# ecocar_CVM_R1.net
KiCad netlist of a schematic drawn in EAGLE
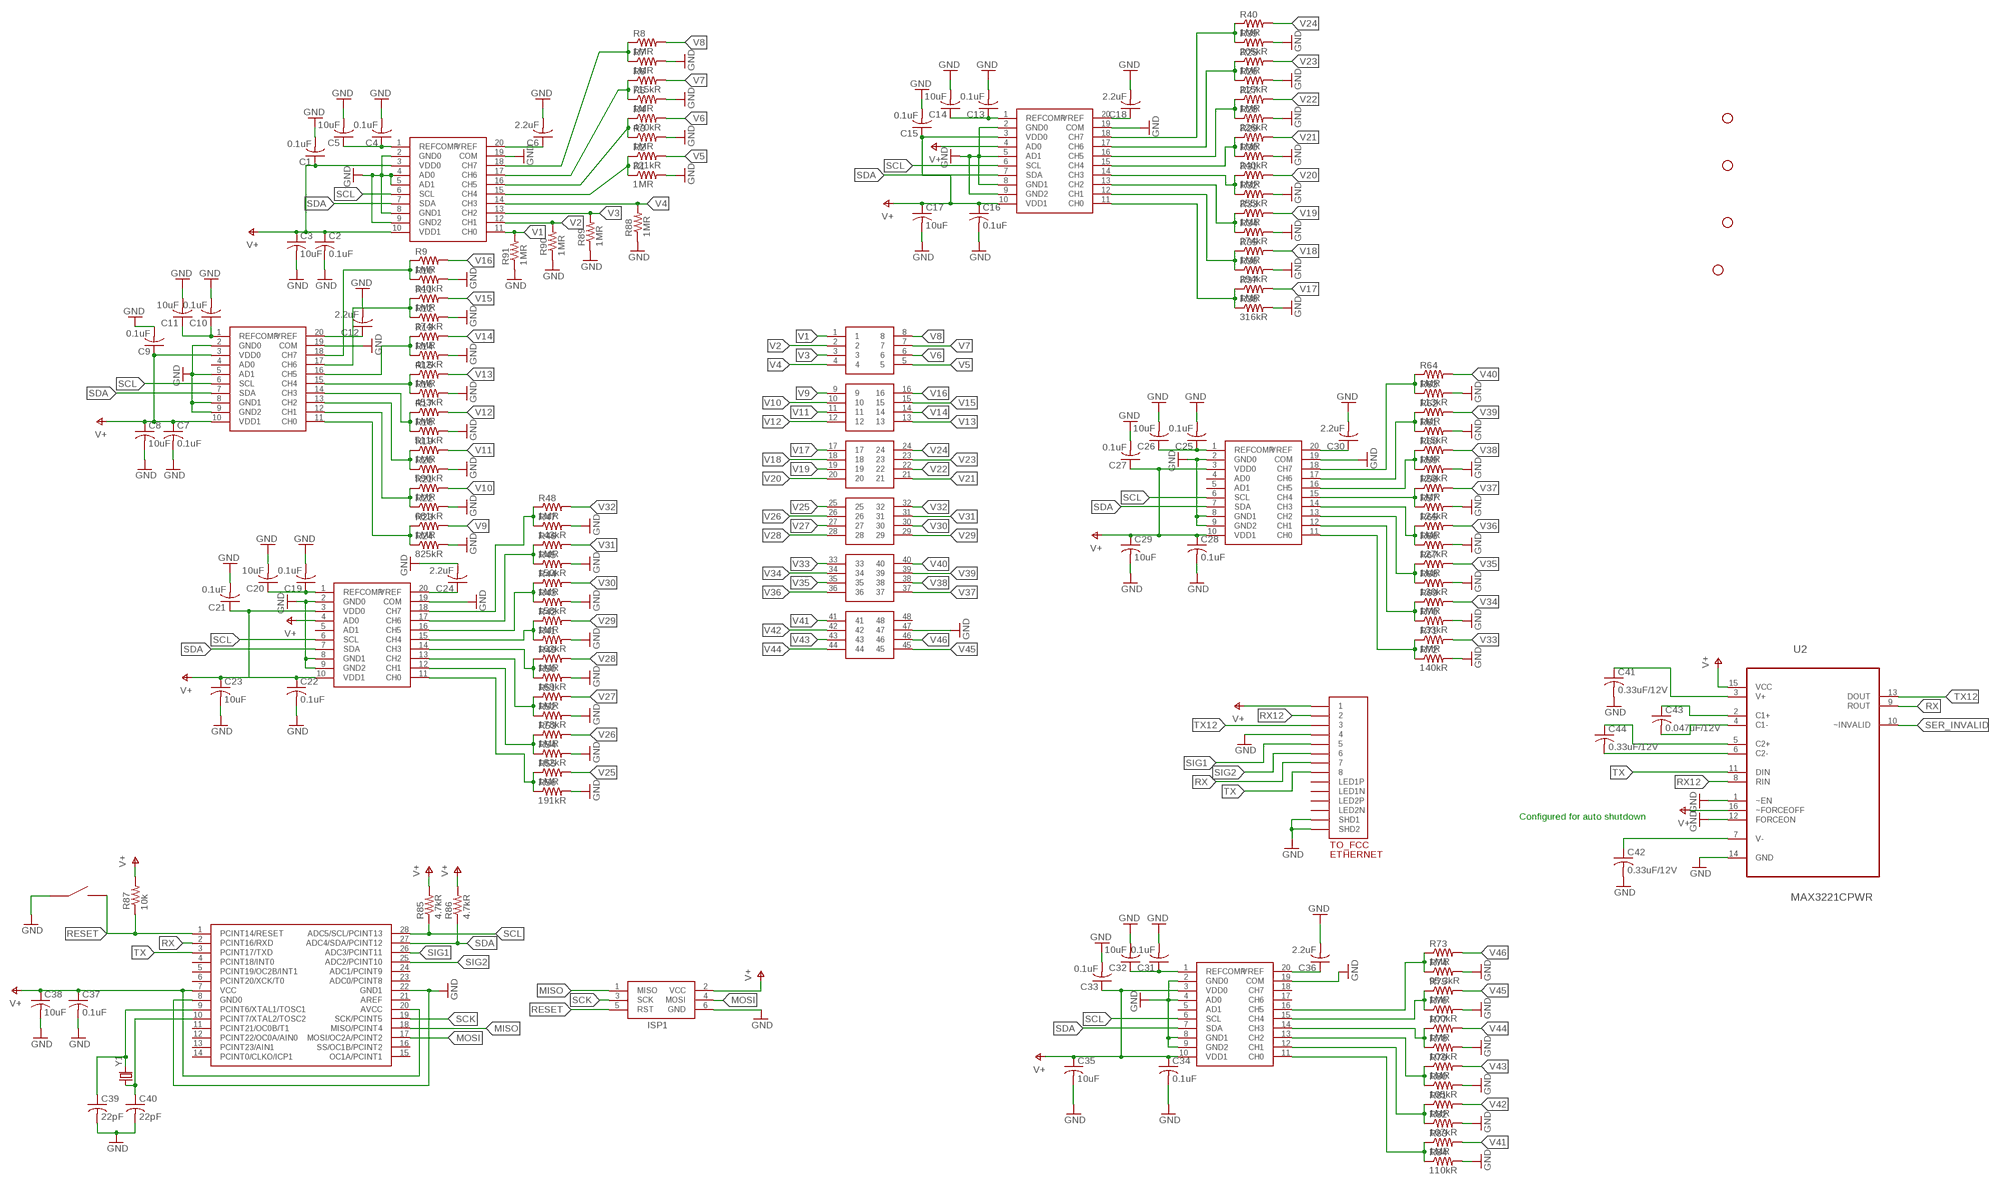
[diagram p0: schematic, sheet 1]

(export (version "E")
  (design (tool "Eeschema 10.0.6"))
  (components
    (comp (ref "0001000")
      (value "LTC2309")
      (footprint "eagle-import:TSSOP20")
      (libsource (lib "eagle-import") (part "LTC2309HF#PBF"))
    )
    (comp (ref "0001001")
      (value "LTC2309")
      (footprint "eagle-import:TSSOP20")
      (libsource (lib "eagle-import") (part "LTC2309HF#PBF"))
    )
    (comp (ref "0001010")
      (value "LTC2309")
      (footprint "eagle-import:TSSOP20")
      (libsource (lib "eagle-import") (part "LTC2309HF#PBF"))
    )
    (comp (ref "0001011")
      (value "LTC2309")
      (footprint "eagle-import:TSSOP20")
      (libsource (lib "eagle-import") (part "LTC2309HF#PBF"))
    )
    (comp (ref "0011000")
      (value "LTC2309")
      (footprint "eagle-import:TSSOP20")
      (libsource (lib "eagle-import") (part "LTC2309HF#PBF"))
    )
    (comp (ref "0011001")
      (value "LTC2309")
      (footprint "eagle-import:TSSOP20")
      (libsource (lib "eagle-import") (part "LTC2309HF#PBF"))
    )
    (comp (ref "C1")
      (value "0.1uF")
      (footprint "eagle-import:C0805")
      (libsource (lib "eagle-import") (part "rcl_C-USC0805"))
    )
    (comp (ref "C2")
      (value "0.1uF")
      (footprint "eagle-import:C0805")
      (libsource (lib "eagle-import") (part "rcl_C-USC0805"))
    )
    (comp (ref "C3")
      (value "10uF")
      (footprint "eagle-import:C0805")
      (libsource (lib "eagle-import") (part "rcl_C-USC0805"))
    )
    (comp (ref "C4")
      (value "0.1uF")
      (footprint "eagle-import:C0805")
      (libsource (lib "eagle-import") (part "rcl_C-USC0805"))
    )
    (comp (ref "C5")
      (value "10uF")
      (footprint "eagle-import:C0805")
      (libsource (lib "eagle-import") (part "rcl_C-USC0805"))
    )
    (comp (ref "C6")
      (value "2.2uF")
      (footprint "eagle-import:C0805")
      (libsource (lib "eagle-import") (part "rcl_C-USC0805"))
    )
    (comp (ref "C7")
      (value "0.1uF")
      (footprint "eagle-import:C0805")
      (libsource (lib "eagle-import") (part "rcl_C-USC0805"))
    )
    (comp (ref "C8")
      (value "10uF")
      (footprint "eagle-import:C0805")
      (libsource (lib "eagle-import") (part "rcl_C-USC0805"))
    )
    (comp (ref "C9")
      (value "0.1uF")
      (footprint "eagle-import:C0805")
      (libsource (lib "eagle-import") (part "rcl_C-USC0805"))
    )
    (comp (ref "C10")
      (value "0.1uF")
      (footprint "eagle-import:C0805")
      (libsource (lib "eagle-import") (part "rcl_C-USC0805"))
    )
    (comp (ref "C11")
      (value "10uF")
      (footprint "eagle-import:C0805")
      (libsource (lib "eagle-import") (part "rcl_C-USC0805"))
    )
    (comp (ref "C12")
      (value "2.2uF")
      (footprint "eagle-import:C0805")
      (libsource (lib "eagle-import") (part "rcl_C-USC0805"))
    )
    (comp (ref "C13")
      (value "0.1uF")
      (footprint "eagle-import:C0805")
      (libsource (lib "eagle-import") (part "rcl_C-USC0805"))
    )
    (comp (ref "C14")
      (value "10uF")
      (footprint "eagle-import:C0805")
      (libsource (lib "eagle-import") (part "rcl_C-USC0805"))
    )
    (comp (ref "C15")
      (value "0.1uF")
      (footprint "eagle-import:C0805")
      (libsource (lib "eagle-import") (part "rcl_C-USC0805"))
    )
    (comp (ref "C16")
      (value "0.1uF")
      (footprint "eagle-import:C0805")
      (libsource (lib "eagle-import") (part "rcl_C-USC0805"))
    )
    (comp (ref "C17")
      (value "10uF")
      (footprint "eagle-import:C0805")
      (libsource (lib "eagle-import") (part "rcl_C-USC0805"))
    )
    (comp (ref "C18")
      (value "2.2uF")
      (footprint "eagle-import:C0805")
      (libsource (lib "eagle-import") (part "rcl_C-USC0805"))
    )
    (comp (ref "C19")
      (value "0.1uF")
      (footprint "eagle-import:C0805")
      (libsource (lib "eagle-import") (part "rcl_C-USC0805"))
    )
    (comp (ref "C20")
      (value "10uF")
      (footprint "eagle-import:C0805")
      (libsource (lib "eagle-import") (part "rcl_C-USC0805"))
    )
    (comp (ref "C21")
      (value "0.1uF")
      (footprint "eagle-import:C0805")
      (libsource (lib "eagle-import") (part "rcl_C-USC0805"))
    )
    (comp (ref "C22")
      (value "0.1uF")
      (footprint "eagle-import:C0805")
      (libsource (lib "eagle-import") (part "rcl_C-USC0805"))
    )
    (comp (ref "C23")
      (value "10uF")
      (footprint "eagle-import:C0805")
      (libsource (lib "eagle-import") (part "rcl_C-USC0805"))
    )
    (comp (ref "C24")
      (value "2.2uF")
      (footprint "eagle-import:C0805")
      (libsource (lib "eagle-import") (part "rcl_C-USC0805"))
    )
    (comp (ref "C25")
      (value "0.1uF")
      (footprint "eagle-import:C0805")
      (libsource (lib "eagle-import") (part "rcl_C-USC0805"))
    )
    (comp (ref "C26")
      (value "10uF")
      (footprint "eagle-import:C0805")
      (libsource (lib "eagle-import") (part "rcl_C-USC0805"))
    )
    (comp (ref "C27")
      (value "0.1uF")
      (footprint "eagle-import:C0805")
      (libsource (lib "eagle-import") (part "rcl_C-USC0805"))
    )
    (comp (ref "C28")
      (value "0.1uF")
      (footprint "eagle-import:C0805")
      (libsource (lib "eagle-import") (part "rcl_C-USC0805"))
    )
    (comp (ref "C29")
      (value "10uF")
      (footprint "eagle-import:C0805")
      (libsource (lib "eagle-import") (part "rcl_C-USC0805"))
    )
    (comp (ref "C30")
      (value "2.2uF")
      (footprint "eagle-import:C0805")
      (libsource (lib "eagle-import") (part "rcl_C-USC0805"))
    )
    (comp (ref "C31")
      (value "0.1uF")
      (footprint "eagle-import:C0805")
      (libsource (lib "eagle-import") (part "rcl_C-USC0805"))
    )
    (comp (ref "C32")
      (value "10uF")
      (footprint "eagle-import:C0805")
      (libsource (lib "eagle-import") (part "rcl_C-USC0805"))
    )
    (comp (ref "C33")
      (value "0.1uF")
      (footprint "eagle-import:C0805")
      (libsource (lib "eagle-import") (part "rcl_C-USC0805"))
    )
    (comp (ref "C34")
      (value "0.1uF")
      (footprint "eagle-import:C0805")
      (libsource (lib "eagle-import") (part "rcl_C-USC0805"))
    )
    (comp (ref "C35")
      (value "10uF")
      (footprint "eagle-import:C0805")
      (libsource (lib "eagle-import") (part "rcl_C-USC0805"))
    )
    (comp (ref "C36")
      (value "2.2uF")
      (footprint "eagle-import:C0805")
      (libsource (lib "eagle-import") (part "rcl_C-USC0805"))
    )
    (comp (ref "C37")
      (value "0.1uF")
      (footprint "eagle-import:C0805")
      (libsource (lib "eagle-import") (part "rcl_C-USC0805"))
    )
    (comp (ref "C38")
      (value "10uF")
      (footprint "eagle-import:C0805")
      (libsource (lib "eagle-import") (part "rcl_C-USC0805"))
    )
    (comp (ref "C39")
      (value "22pF")
      (footprint "eagle-import:C0805")
      (libsource (lib "eagle-import") (part "rcl_C-USC0805"))
    )
    (comp (ref "C40")
      (value "22pF")
      (footprint "eagle-import:C0805")
      (libsource (lib "eagle-import") (part "rcl_C-USC0805"))
    )
    (comp (ref "C41")
      (value "0.33uF/12V")
      (footprint "eagle-import:C0805")
      (libsource (lib "eagle-import") (part "C-USC0805"))
    )
    (comp (ref "C42")
      (value "0.33uF/12V")
      (footprint "eagle-import:C0805")
      (libsource (lib "eagle-import") (part "C-USC0805"))
    )
    (comp (ref "C43")
      (value "0.047uF/12V")
      (footprint "eagle-import:C0805")
      (libsource (lib "eagle-import") (part "C-USC0805"))
    )
    (comp (ref "C44")
      (value "0.33uF/12V")
      (footprint "eagle-import:C0805")
      (libsource (lib "eagle-import") (part "C-USC0805"))
    )
    (comp (ref "ISP1")
      (value "AVRISP-BOX")
      (footprint "eagle-import:AVRISP-BOX")
      (libsource (lib "eagle-import") (part "AVRISP-BOX"))
    )
    (comp (ref "R1")
      (value "1MR")
      (footprint "eagle-import:R0805")
      (libsource (lib "eagle-import") (part "R-US_R0805"))
    )
    (comp (ref "R2")
      (value "221kR")
      (footprint "eagle-import:R0805")
      (libsource (lib "eagle-import") (part "R-US_R0805"))
    )
    (comp (ref "R3")
      (value "1MR")
      (footprint "eagle-import:R0805")
      (libsource (lib "eagle-import") (part "R-US_R0805"))
    )
    (comp (ref "R4")
      (value "470kR")
      (footprint "eagle-import:R0805")
      (libsource (lib "eagle-import") (part "R-US_R0805"))
    )
    (comp (ref "R5")
      (value "1MR")
      (footprint "eagle-import:R0805")
      (libsource (lib "eagle-import") (part "R-US_R0805"))
    )
    (comp (ref "R6")
      (value "715kR")
      (footprint "eagle-import:R0805")
      (libsource (lib "eagle-import") (part "R-US_R0805"))
    )
    (comp (ref "R7")
      (value "1MR")
      (footprint "eagle-import:R0805")
      (libsource (lib "eagle-import") (part "R-US_R0805"))
    )
    (comp (ref "R8")
      (value "1MR")
      (footprint "eagle-import:R0805")
      (libsource (lib "eagle-import") (part "R-US_R0805"))
    )
    (comp (ref "R9")
      (value "1MR")
      (footprint "eagle-import:R0805")
      (libsource (lib "eagle-import") (part "R-US_R0805"))
    )
    (comp (ref "R10")
      (value "340kR")
      (footprint "eagle-import:R0805")
      (libsource (lib "eagle-import") (part "R-US_R0805"))
    )
    (comp (ref "R11")
      (value "1MR")
      (footprint "eagle-import:R0805")
      (libsource (lib "eagle-import") (part "R-US_R0805"))
    )
    (comp (ref "R12")
      (value "374kR")
      (footprint "eagle-import:R0805")
      (libsource (lib "eagle-import") (part "R-US_R0805"))
    )
    (comp (ref "R13")
      (value "1MR")
      (footprint "eagle-import:R0805")
      (libsource (lib "eagle-import") (part "R-US_R0805"))
    )
    (comp (ref "R14")
      (value "412kR")
      (footprint "eagle-import:R0805")
      (libsource (lib "eagle-import") (part "R-US_R0805"))
    )
    (comp (ref "R15")
      (value "1MR")
      (footprint "eagle-import:R0805")
      (libsource (lib "eagle-import") (part "R-US_R0805"))
    )
    (comp (ref "R16")
      (value "453kR")
      (footprint "eagle-import:R0805")
      (libsource (lib "eagle-import") (part "R-US_R0805"))
    )
    (comp (ref "R17")
      (value "1MR")
      (footprint "eagle-import:R0805")
      (libsource (lib "eagle-import") (part "R-US_R0805"))
    )
    (comp (ref "R18")
      (value "511kR")
      (footprint "eagle-import:R0805")
      (libsource (lib "eagle-import") (part "R-US_R0805"))
    )
    (comp (ref "R19")
      (value "1MR")
      (footprint "eagle-import:R0805")
      (libsource (lib "eagle-import") (part "R-US_R0805"))
    )
    (comp (ref "R20")
      (value "590kR")
      (footprint "eagle-import:R0805")
      (libsource (lib "eagle-import") (part "R-US_R0805"))
    )
    (comp (ref "R21")
      (value "1MR")
      (footprint "eagle-import:R0805")
      (libsource (lib "eagle-import") (part "R-US_R0805"))
    )
    (comp (ref "R22")
      (value "681kR")
      (footprint "eagle-import:R0805")
      (libsource (lib "eagle-import") (part "R-US_R0805"))
    )
    (comp (ref "R23")
      (value "1MR")
      (footprint "eagle-import:R0805")
      (libsource (lib "eagle-import") (part "R-US_R0805"))
    )
    (comp (ref "R24")
      (value "825kR")
      (footprint "eagle-import:R0805")
      (libsource (lib "eagle-import") (part "R-US_R0805"))
    )
    (comp (ref "R25")
      (value "1MR")
      (footprint "eagle-import:R0805")
      (libsource (lib "eagle-import") (part "R-US_R0805"))
    )
    (comp (ref "R26")
      (value "215kR")
      (footprint "eagle-import:R0805")
      (libsource (lib "eagle-import") (part "R-US_R0805"))
    )
    (comp (ref "R27")
      (value "1MR")
      (footprint "eagle-import:R0805")
      (libsource (lib "eagle-import") (part "R-US_R0805"))
    )
    (comp (ref "R28")
      (value "226kR")
      (footprint "eagle-import:R0805")
      (libsource (lib "eagle-import") (part "R-US_R0805"))
    )
    (comp (ref "R29")
      (value "1MR")
      (footprint "eagle-import:R0805")
      (libsource (lib "eagle-import") (part "R-US_R0805"))
    )
    (comp (ref "R30")
      (value "240kR")
      (footprint "eagle-import:R0805")
      (libsource (lib "eagle-import") (part "R-US_R0805"))
    )
    (comp (ref "R31")
      (value "1MR")
      (footprint "eagle-import:R0805")
      (libsource (lib "eagle-import") (part "R-US_R0805"))
    )
    (comp (ref "R32")
      (value "255kR")
      (footprint "eagle-import:R0805")
      (libsource (lib "eagle-import") (part "R-US_R0805"))
    )
    (comp (ref "R33")
      (value "1MR")
      (footprint "eagle-import:R0805")
      (libsource (lib "eagle-import") (part "R-US_R0805"))
    )
    (comp (ref "R34")
      (value "274kR")
      (footprint "eagle-import:R0805")
      (libsource (lib "eagle-import") (part "R-US_R0805"))
    )
    (comp (ref "R35")
      (value "1MR")
      (footprint "eagle-import:R0805")
      (libsource (lib "eagle-import") (part "R-US_R0805"))
    )
    (comp (ref "R36")
      (value "294kR")
      (footprint "eagle-import:R0805")
      (libsource (lib "eagle-import") (part "R-US_R0805"))
    )
    (comp (ref "R37")
      (value "1MR")
      (footprint "eagle-import:R0805")
      (libsource (lib "eagle-import") (part "R-US_R0805"))
    )
    (comp (ref "R38")
      (value "316kR")
      (footprint "eagle-import:R0805")
      (libsource (lib "eagle-import") (part "R-US_R0805"))
    )
    (comp (ref "R39")
      (value "205kR")
      (footprint "eagle-import:R0805")
      (libsource (lib "eagle-import") (part "R-US_R0805"))
    )
    (comp (ref "R40")
      (value "1MR")
      (footprint "eagle-import:R0805")
      (libsource (lib "eagle-import") (part "R-US_R0805"))
    )
    (comp (ref "R41")
      (value "162kR")
      (footprint "eagle-import:R0805")
      (libsource (lib "eagle-import") (part "R-US_R0805"))
    )
    (comp (ref "R42")
      (value "1MR")
      (footprint "eagle-import:R0805")
      (libsource (lib "eagle-import") (part "R-US_R0805"))
    )
    (comp (ref "R43")
      (value "158kR")
      (footprint "eagle-import:R0805")
      (libsource (lib "eagle-import") (part "R-US_R0805"))
    )
    (comp (ref "R44")
      (value "1MR")
      (footprint "eagle-import:R0805")
      (libsource (lib "eagle-import") (part "R-US_R0805"))
    )
    (comp (ref "R45")
      (value "150kR")
      (footprint "eagle-import:R0805")
      (libsource (lib "eagle-import") (part "R-US_R0805"))
    )
    (comp (ref "R46")
      (value "1MR")
      (footprint "eagle-import:R0805")
      (libsource (lib "eagle-import") (part "R-US_R0805"))
    )
    (comp (ref "R47")
      (value "143kR")
      (footprint "eagle-import:R0805")
      (libsource (lib "eagle-import") (part "R-US_R0805"))
    )
    (comp (ref "R48")
      (value "1MR")
      (footprint "eagle-import:R0805")
      (libsource (lib "eagle-import") (part "R-US_R0805"))
    )
    (comp (ref "R49")
      (value "1MR")
      (footprint "eagle-import:R0805")
      (libsource (lib "eagle-import") (part "R-US_R0805"))
    )
    (comp (ref "R50")
      (value "169kR")
      (footprint "eagle-import:R0805")
      (libsource (lib "eagle-import") (part "R-US_R0805"))
    )
    (comp (ref "R51")
      (value "1MR")
      (footprint "eagle-import:R0805")
      (libsource (lib "eagle-import") (part "R-US_R0805"))
    )
    (comp (ref "R52")
      (value "178kR")
      (footprint "eagle-import:R0805")
      (libsource (lib "eagle-import") (part "R-US_R0805"))
    )
    (comp (ref "R53")
      (value "1MR")
      (footprint "eagle-import:R0805")
      (libsource (lib "eagle-import") (part "R-US_R0805"))
    )
    (comp (ref "R54")
      (value "182kR")
      (footprint "eagle-import:R0805")
      (libsource (lib "eagle-import") (part "R-US_R0805"))
    )
    (comp (ref "R55")
      (value "1MR")
      (footprint "eagle-import:R0805")
      (libsource (lib "eagle-import") (part "R-US_R0805"))
    )
    (comp (ref "R56")
      (value "191kR")
      (footprint "eagle-import:R0805")
      (libsource (lib "eagle-import") (part "R-US_R0805"))
    )
    (comp (ref "R57")
      (value "124kR")
      (footprint "eagle-import:R0805")
      (libsource (lib "eagle-import") (part "R-US_R0805"))
    )
    (comp (ref "R58")
      (value "1MR")
      (footprint "eagle-import:R0805")
      (libsource (lib "eagle-import") (part "R-US_R0805"))
    )
    (comp (ref "R59")
      (value "120kR")
      (footprint "eagle-import:R0805")
      (libsource (lib "eagle-import") (part "R-US_R0805"))
    )
    (comp (ref "R60")
      (value "1MR")
      (footprint "eagle-import:R0805")
      (libsource (lib "eagle-import") (part "R-US_R0805"))
    )
    (comp (ref "R61")
      (value "115kR")
      (footprint "eagle-import:R0805")
      (libsource (lib "eagle-import") (part "R-US_R0805"))
    )
    (comp (ref "R62")
      (value "1MR")
      (footprint "eagle-import:R0805")
      (libsource (lib "eagle-import") (part "R-US_R0805"))
    )
    (comp (ref "R63")
      (value "113kR")
      (footprint "eagle-import:R0805")
      (libsource (lib "eagle-import") (part "R-US_R0805"))
    )
    (comp (ref "R64")
      (value "1MR")
      (footprint "eagle-import:R0805")
      (libsource (lib "eagle-import") (part "R-US_R0805"))
    )
    (comp (ref "R65")
      (value "1MR")
      (footprint "eagle-import:R0805")
      (libsource (lib "eagle-import") (part "R-US_R0805"))
    )
    (comp (ref "R66")
      (value "127kR")
      (footprint "eagle-import:R0805")
      (libsource (lib "eagle-import") (part "R-US_R0805"))
    )
    (comp (ref "R67")
      (value "1MR")
      (footprint "eagle-import:R0805")
      (libsource (lib "eagle-import") (part "R-US_R0805"))
    )
    (comp (ref "R68")
      (value "130kR")
      (footprint "eagle-import:R0805")
      (libsource (lib "eagle-import") (part "R-US_R0805"))
    )
    (comp (ref "R69")
      (value "1MR")
      (footprint "eagle-import:R0805")
      (libsource (lib "eagle-import") (part "R-US_R0805"))
    )
    (comp (ref "R70")
      (value "133kR")
      (footprint "eagle-import:R0805")
      (libsource (lib "eagle-import") (part "R-US_R0805"))
    )
    (comp (ref "R71")
      (value "1MR")
      (footprint "eagle-import:R0805")
      (libsource (lib "eagle-import") (part "R-US_R0805"))
    )
    (comp (ref "R72")
      (value "140kR")
      (footprint "eagle-import:R0805")
      (libsource (lib "eagle-import") (part "R-US_R0805"))
    )
    (comp (ref "R73")
      (value "1MR")
      (footprint "eagle-import:R0805")
      (libsource (lib "eagle-import") (part "R-US_R0805"))
    )
    (comp (ref "R74")
      (value "95.3kR")
      (footprint "eagle-import:R0805")
      (libsource (lib "eagle-import") (part "R-US_R0805"))
    )
    (comp (ref "R75")
      (value "1MR")
      (footprint "eagle-import:R0805")
      (libsource (lib "eagle-import") (part "R-US_R0805"))
    )
    (comp (ref "R76")
      (value "100kR")
      (footprint "eagle-import:R0805")
      (libsource (lib "eagle-import") (part "R-US_R0805"))
    )
    (comp (ref "R77")
      (value "1MR")
      (footprint "eagle-import:R0805")
      (libsource (lib "eagle-import") (part "R-US_R0805"))
    )
    (comp (ref "R78")
      (value "102kR")
      (footprint "eagle-import:R0805")
      (libsource (lib "eagle-import") (part "R-US_R0805"))
    )
    (comp (ref "R79")
      (value "1MR")
      (footprint "eagle-import:R0805")
      (libsource (lib "eagle-import") (part "R-US_R0805"))
    )
    (comp (ref "R80")
      (value "105kR")
      (footprint "eagle-import:R0805")
      (libsource (lib "eagle-import") (part "R-US_R0805"))
    )
    (comp (ref "R81")
      (value "1MR")
      (footprint "eagle-import:R0805")
      (libsource (lib "eagle-import") (part "R-US_R0805"))
    )
    (comp (ref "R82")
      (value "107kR")
      (footprint "eagle-import:R0805")
      (libsource (lib "eagle-import") (part "R-US_R0805"))
    )
    (comp (ref "R83")
      (value "1MR")
      (footprint "eagle-import:R0805")
      (libsource (lib "eagle-import") (part "R-US_R0805"))
    )
    (comp (ref "R84")
      (value "110kR")
      (footprint "eagle-import:R0805")
      (libsource (lib "eagle-import") (part "R-US_R0805"))
    )
    (comp (ref "R85")
      (value "4.7kR")
      (footprint "eagle-import:R0805")
      (libsource (lib "eagle-import") (part "R-US_R0805"))
    )
    (comp (ref "R86")
      (value "4.7kR")
      (footprint "eagle-import:R0805")
      (libsource (lib "eagle-import") (part "R-US_R0805"))
    )
    (comp (ref "R87")
      (value "10k")
      (footprint "eagle-import:R0805")
      (libsource (lib "eagle-import") (part "R-US_R0805"))
    )
    (comp (ref "R88")
      (value "1MR")
      (footprint "eagle-import:R0805")
      (libsource (lib "eagle-import") (part "R-US_R0805"))
    )
    (comp (ref "R89")
      (value "1MR")
      (footprint "eagle-import:R0805")
      (libsource (lib "eagle-import") (part "R-US_R0805"))
    )
    (comp (ref "R90")
      (value "1MR")
      (footprint "eagle-import:R0805")
      (libsource (lib "eagle-import") (part "R-US_R0805"))
    )
    (comp (ref "R91")
      (value "1MR")
      (footprint "eagle-import:R0805")
      (libsource (lib "eagle-import") (part "R-US_R0805"))
    )
    (comp (ref "RESET_BTN")
      (value "EG4621CT-ND")
      (footprint "eagle-import:EG4621CT-ND")
      (libsource (lib "eagle-import") (part "EG4621CT-ND"))
    )
    (comp (ref "STANDOFF1")
      (value "STAND-OFF")
      (footprint "eagle-import:STAND-OFF")
      (libsource (lib "eagle-import") (part "STAND-OFF"))
    )
    (comp (ref "STANDOFF2")
      (value "STAND-OFF")
      (footprint "eagle-import:STAND-OFF")
      (libsource (lib "eagle-import") (part "STAND-OFF"))
    )
    (comp (ref "STANDOFF3")
      (value "STAND-OFF")
      (footprint "eagle-import:STAND-OFF")
      (libsource (lib "eagle-import") (part "STAND-OFF"))
    )
    (comp (ref "STANDOFF4")
      (value "STAND-OFF")
      (footprint "eagle-import:STAND-OFF")
      (libsource (lib "eagle-import") (part "STAND-OFF"))
    )
    (comp (ref "TO_FCC")
      (value "ETHERNET")
      (footprint "eagle-import:A122645-ND")
      (libsource (lib "eagle-import") (part "ETHERNET"))
    )
    (comp (ref "U$1")
      (value "ATMEGA328P")
      (footprint "eagle-import:DIL28-3")
      (libsource (lib "eagle-import") (part "ATMEGA328P"))
    )
    (comp (ref "U$3")
      (value "6-RJ45")
      (footprint "eagle-import:48-PIN-THROUGHHOLE")
      (libsource (lib "eagle-import") (part "6-RJ45-5557572-3"))
    )
    (comp (ref "U2")
      (value "MAX3221CPWR")
      (footprint "eagle-import:SOP65P640X120-16N")
      (libsource (lib "eagle-import") (part "MAX3221CPWR"))
    )
    (comp (ref "Y1")
      (value "CRYSTALHC49US")
      (footprint "eagle-import:HC49US")
      (libsource (lib "eagle-import") (part "CRYSTALHC49US"))
    )
  )
  (nets
    (net (code "1") (name "GND") (class "Default")
      (node (ref "0001000") (pin "19") (pinfunction "COM_19") (pintype "bidirectional"))
      (node (ref "0001000") (pin "2") (pinfunction "GND0_2") (pintype "bidirectional"))
      (node (ref "0001000") (pin "4") (pinfunction "AD0_4") (pintype "bidirectional"))
      (node (ref "0001000") (pin "5") (pinfunction "AD1_5") (pintype "bidirectional"))
      (node (ref "0001000") (pin "8") (pinfunction "GND1_8") (pintype "bidirectional"))
      (node (ref "0001000") (pin "9") (pinfunction "GND2_9") (pintype "bidirectional"))
      (node (ref "0001001") (pin "19") (pinfunction "COM_19") (pintype "bidirectional"))
      (node (ref "0001001") (pin "2") (pinfunction "GND0_2") (pintype "bidirectional"))
      (node (ref "0001001") (pin "5") (pinfunction "AD1_5") (pintype "bidirectional"))
      (node (ref "0001001") (pin "8") (pinfunction "GND1_8") (pintype "bidirectional"))
      (node (ref "0001001") (pin "9") (pinfunction "GND2_9") (pintype "bidirectional"))
      (node (ref "0001010") (pin "19") (pinfunction "COM_19") (pintype "bidirectional"))
      (node (ref "0001010") (pin "2") (pinfunction "GND0_2") (pintype "bidirectional"))
      (node (ref "0001010") (pin "5") (pinfunction "AD1_5") (pintype "bidirectional"))
      (node (ref "0001010") (pin "8") (pinfunction "GND1_8") (pintype "bidirectional"))
      (node (ref "0001010") (pin "9") (pinfunction "GND2_9") (pintype "bidirectional"))
      (node (ref "0001011") (pin "19") (pinfunction "COM_19") (pintype "bidirectional"))
      (node (ref "0001011") (pin "2") (pinfunction "GND0_2") (pintype "bidirectional"))
      (node (ref "0001011") (pin "8") (pinfunction "GND1_8") (pintype "bidirectional"))
      (node (ref "0001011") (pin "9") (pinfunction "GND2_9") (pintype "bidirectional"))
      (node (ref "0011000") (pin "19") (pinfunction "COM_19") (pintype "bidirectional"))
      (node (ref "0011000") (pin "2") (pinfunction "GND0_2") (pintype "bidirectional"))
      (node (ref "0011000") (pin "8") (pinfunction "GND1_8") (pintype "bidirectional"))
      (node (ref "0011000") (pin "9") (pinfunction "GND2_9") (pintype "bidirectional"))
      (node (ref "0011001") (pin "19") (pinfunction "COM_19") (pintype "bidirectional"))
      (node (ref "0011001") (pin "2") (pinfunction "GND0_2") (pintype "bidirectional"))
      (node (ref "0011001") (pin "4") (pinfunction "AD0_4") (pintype "bidirectional"))
      (node (ref "0011001") (pin "8") (pinfunction "GND1_8") (pintype "bidirectional"))
      (node (ref "0011001") (pin "9") (pinfunction "GND2_9") (pintype "bidirectional"))
      (node (ref "C1") (pin "2") (pinfunction "2_2") (pintype "passive"))
      (node (ref "C10") (pin "2") (pinfunction "2_2") (pintype "passive"))
      (node (ref "C11") (pin "2") (pinfunction "2_2") (pintype "passive"))
      (node (ref "C12") (pin "2") (pinfunction "2_2") (pintype "passive"))
      (node (ref "C13") (pin "2") (pinfunction "2_2") (pintype "passive"))
      (node (ref "C14") (pin "2") (pinfunction "2_2") (pintype "passive"))
      (node (ref "C15") (pin "2") (pinfunction "2_2") (pintype "passive"))
      (node (ref "C16") (pin "2") (pinfunction "2_2") (pintype "passive"))
      (node (ref "C17") (pin "2") (pinfunction "2_2") (pintype "passive"))
      (node (ref "C18") (pin "2") (pinfunction "2_2") (pintype "passive"))
      (node (ref "C19") (pin "2") (pinfunction "2_2") (pintype "passive"))
      (node (ref "C2") (pin "2") (pinfunction "2_2") (pintype "passive"))
      (node (ref "C20") (pin "2") (pinfunction "2_2") (pintype "passive"))
      (node (ref "C21") (pin "2") (pinfunction "2_2") (pintype "passive"))
      (node (ref "C22") (pin "2") (pinfunction "2_2") (pintype "passive"))
      (node (ref "C23") (pin "2") (pinfunction "2_2") (pintype "passive"))
      (node (ref "C24") (pin "2") (pinfunction "2_2") (pintype "passive"))
      (node (ref "C25") (pin "2") (pinfunction "2_2") (pintype "passive"))
      (node (ref "C26") (pin "2") (pinfunction "2_2") (pintype "passive"))
      (node (ref "C27") (pin "2") (pinfunction "2_2") (pintype "passive"))
      (node (ref "C28") (pin "2") (pinfunction "2_2") (pintype "passive"))
      (node (ref "C29") (pin "2") (pinfunction "2_2") (pintype "passive"))
      (node (ref "C3") (pin "2") (pinfunction "2_2") (pintype "passive"))
      (node (ref "C30") (pin "2") (pinfunction "2_2") (pintype "passive"))
      (node (ref "C31") (pin "2") (pinfunction "2_2") (pintype "passive"))
      (node (ref "C32") (pin "2") (pinfunction "2_2") (pintype "passive"))
      (node (ref "C33") (pin "2") (pinfunction "2_2") (pintype "passive"))
      (node (ref "C34") (pin "2") (pinfunction "2_2") (pintype "passive"))
      (node (ref "C35") (pin "2") (pinfunction "2_2") (pintype "passive"))
      (node (ref "C36") (pin "2") (pinfunction "2_2") (pintype "passive"))
      (node (ref "C37") (pin "2") (pinfunction "2_2") (pintype "passive"))
      (node (ref "C38") (pin "2") (pinfunction "2_2") (pintype "passive"))
      (node (ref "C39") (pin "2") (pinfunction "2_2") (pintype "passive"))
      (node (ref "C4") (pin "2") (pinfunction "2_2") (pintype "passive"))
      (node (ref "C40") (pin "2") (pinfunction "2_2") (pintype "passive"))
      (node (ref "C41") (pin "2") (pinfunction "2_2") (pintype "passive"))
      (node (ref "C42") (pin "2") (pinfunction "2_2") (pintype "passive"))
      (node (ref "C5") (pin "2") (pinfunction "2_2") (pintype "passive"))
      (node (ref "C6") (pin "2") (pinfunction "2_2") (pintype "passive"))
      (node (ref "C7") (pin "2") (pinfunction "2_2") (pintype "passive"))
      (node (ref "C8") (pin "2") (pinfunction "2_2") (pintype "passive"))
      (node (ref "C9") (pin "2") (pinfunction "2_2") (pintype "passive"))
      (node (ref "ISP1") (pin "6") (pinfunction "GND_6") (pintype "power_in"))
      (node (ref "R1") (pin "2") (pinfunction "2_2") (pintype "passive"))
      (node (ref "R10") (pin "2") (pinfunction "2_2") (pintype "passive"))
      (node (ref "R12") (pin "2") (pinfunction "2_2") (pintype "passive"))
      (node (ref "R14") (pin "2") (pinfunction "2_2") (pintype "passive"))
      (node (ref "R16") (pin "2") (pinfunction "2_2") (pintype "passive"))
      (node (ref "R18") (pin "2") (pinfunction "2_2") (pintype "passive"))
      (node (ref "R20") (pin "2") (pinfunction "2_2") (pintype "passive"))
      (node (ref "R22") (pin "2") (pinfunction "2_2") (pintype "passive"))
      (node (ref "R24") (pin "2") (pinfunction "2_2") (pintype "passive"))
      (node (ref "R26") (pin "2") (pinfunction "2_2") (pintype "passive"))
      (node (ref "R28") (pin "2") (pinfunction "2_2") (pintype "passive"))
      (node (ref "R3") (pin "2") (pinfunction "2_2") (pintype "passive"))
      (node (ref "R30") (pin "2") (pinfunction "2_2") (pintype "passive"))
      (node (ref "R32") (pin "2") (pinfunction "2_2") (pintype "passive"))
      (node (ref "R34") (pin "2") (pinfunction "2_2") (pintype "passive"))
      (node (ref "R36") (pin "2") (pinfunction "2_2") (pintype "passive"))
      (node (ref "R38") (pin "2") (pinfunction "2_2") (pintype "passive"))
      (node (ref "R39") (pin "2") (pinfunction "2_2") (pintype "passive"))
      (node (ref "R41") (pin "2") (pinfunction "2_2") (pintype "passive"))
      (node (ref "R43") (pin "2") (pinfunction "2_2") (pintype "passive"))
      (node (ref "R45") (pin "2") (pinfunction "2_2") (pintype "passive"))
      (node (ref "R47") (pin "2") (pinfunction "2_2") (pintype "passive"))
      (node (ref "R5") (pin "2") (pinfunction "2_2") (pintype "passive"))
      (node (ref "R50") (pin "2") (pinfunction "2_2") (pintype "passive"))
      (node (ref "R52") (pin "2") (pinfunction "2_2") (pintype "passive"))
      (node (ref "R54") (pin "2") (pinfunction "2_2") (pintype "passive"))
      (node (ref "R56") (pin "2") (pinfunction "2_2") (pintype "passive"))
      (node (ref "R57") (pin "2") (pinfunction "2_2") (pintype "passive"))
      (node (ref "R59") (pin "2") (pinfunction "2_2") (pintype "passive"))
      (node (ref "R61") (pin "2") (pinfunction "2_2") (pintype "passive"))
      (node (ref "R63") (pin "2") (pinfunction "2_2") (pintype "passive"))
      (node (ref "R66") (pin "2") (pinfunction "2_2") (pintype "passive"))
      (node (ref "R68") (pin "2") (pinfunction "2_2") (pintype "passive"))
      (node (ref "R7") (pin "2") (pinfunction "2_2") (pintype "passive"))
      (node (ref "R70") (pin "2") (pinfunction "2_2") (pintype "passive"))
      (node (ref "R72") (pin "2") (pinfunction "2_2") (pintype "passive"))
      (node (ref "R74") (pin "2") (pinfunction "2_2") (pintype "passive"))
      (node (ref "R76") (pin "2") (pinfunction "2_2") (pintype "passive"))
      (node (ref "R78") (pin "2") (pinfunction "2_2") (pintype "passive"))
      (node (ref "R80") (pin "2") (pinfunction "2_2") (pintype "passive"))
      (node (ref "R82") (pin "2") (pinfunction "2_2") (pintype "passive"))
      (node (ref "R84") (pin "2") (pinfunction "2_2") (pintype "passive"))
      (node (ref "R88") (pin "1") (pinfunction "1_1") (pintype "passive"))
      (node (ref "R89") (pin "1") (pinfunction "1_1") (pintype "passive"))
      (node (ref "R90") (pin "1") (pinfunction "1_1") (pintype "passive"))
      (node (ref "R91") (pin "1") (pinfunction "1_1") (pintype "passive"))
      (node (ref "RESET_BTN") (pin "P$1") (pinfunction "P$1_P$1") (pintype "bidirectional"))
      (node (ref "RESET_BTN") (pin "P$2") (pinfunction "P$1_P$2") (pintype "bidirectional"))
      (node (ref "TO_FCC") (pin "P$13") (pinfunction "SHD1_P$13") (pintype "bidirectional"))
      (node (ref "TO_FCC") (pin "P$14") (pinfunction "SHD2_P$14") (pintype "bidirectional"))
      (node (ref "TO_FCC") (pin "P$4") (pinfunction "4_P$4") (pintype "bidirectional"))
      (node (ref "U$1") (pin "22") (pinfunction "GND1_22") (pintype "bidirectional"))
      (node (ref "U$1") (pin "8") (pinfunction "GND0_8") (pintype "bidirectional"))
      (node (ref "U$3") (pin "47") (pinfunction "47_47") (pintype "bidirectional"))
      (node (ref "U2") (pin "1") (pinfunction "~{EN}_1") (pintype "input"))
      (node (ref "U2") (pin "12") (pinfunction "FORCEON_12") (pintype "input"))
      (node (ref "U2") (pin "14") (pinfunction "GND_14") (pintype "passive"))
    )
    (net (code "2") (name "MISO") (class "Default")
      (node (ref "ISP1") (pin "1") (pinfunction "MISO_1") (pintype "input"))
      (node (ref "U$1") (pin "18") (pinfunction "MISO/PCINT4_18") (pintype "bidirectional"))
    )
    (net (code "3") (name "MOSI") (class "Default")
      (node (ref "ISP1") (pin "4") (pinfunction "MOSI_4") (pintype "output"))
      (node (ref "U$1") (pin "17") (pinfunction "MOSI/OC2A/PCINT2_17") (pintype "bidirectional"))
    )
    (net (code "4") (name "Net-(0001000-CH4)") (class "Default")
      (node (ref "0001000") (pin "15") (pinfunction "CH4_15") (pintype "bidirectional"))
      (node (ref "R1") (pin "1") (pinfunction "1_1") (pintype "passive"))
      (node (ref "R2") (pin "1") (pinfunction "1_1") (pintype "passive"))
    )
    (net (code "5") (name "Net-(0001000-CH5)") (class "Default")
      (node (ref "0001000") (pin "16") (pinfunction "CH5_16") (pintype "bidirectional"))
      (node (ref "R3") (pin "1") (pinfunction "1_1") (pintype "passive"))
      (node (ref "R4") (pin "1") (pinfunction "1_1") (pintype "passive"))
    )
    (net (code "6") (name "Net-(0001000-CH6)") (class "Default")
      (node (ref "0001000") (pin "17") (pinfunction "CH6_17") (pintype "bidirectional"))
      (node (ref "R5") (pin "1") (pinfunction "1_1") (pintype "passive"))
      (node (ref "R6") (pin "1") (pinfunction "1_1") (pintype "passive"))
    )
    (net (code "7") (name "Net-(0001000-CH7)") (class "Default")
      (node (ref "0001000") (pin "18") (pinfunction "CH7_18") (pintype "bidirectional"))
      (node (ref "R7") (pin "1") (pinfunction "1_1") (pintype "passive"))
      (node (ref "R8") (pin "1") (pinfunction "1_1") (pintype "passive"))
    )
    (net (code "8") (name "Net-(0001000-REFCOMP)") (class "Default")
      (node (ref "0001000") (pin "1") (pinfunction "REFCOMP_1") (pintype "bidirectional"))
      (node (ref "C4") (pin "1") (pinfunction "1_1") (pintype "passive"))
      (node (ref "C5") (pin "1") (pinfunction "1_1") (pintype "passive"))
    )
    (net (code "9") (name "Net-(0001000-VREF)") (class "Default")
      (node (ref "0001000") (pin "20") (pinfunction "VREF_20") (pintype "bidirectional"))
      (node (ref "C6") (pin "1") (pinfunction "1_1") (pintype "passive"))
    )
    (net (code "10") (name "Net-(0001001-CH0)") (class "Default")
      (node (ref "0001001") (pin "11") (pinfunction "CH0_11") (pintype "bidirectional"))
      (node (ref "R23") (pin "1") (pinfunction "1_1") (pintype "passive"))
      (node (ref "R24") (pin "1") (pinfunction "1_1") (pintype "passive"))
    )
    (net (code "11") (name "Net-(0001001-CH1)") (class "Default")
      (node (ref "0001001") (pin "12") (pinfunction "CH1_12") (pintype "bidirectional"))
      (node (ref "R21") (pin "1") (pinfunction "1_1") (pintype "passive"))
      (node (ref "R22") (pin "1") (pinfunction "1_1") (pintype "passive"))
    )
    (net (code "12") (name "Net-(0001001-CH2)") (class "Default")
      (node (ref "0001001") (pin "13") (pinfunction "CH2_13") (pintype "bidirectional"))
      (node (ref "R19") (pin "1") (pinfunction "1_1") (pintype "passive"))
      (node (ref "R20") (pin "1") (pinfunction "1_1") (pintype "passive"))
    )
    (net (code "13") (name "Net-(0001001-CH3)") (class "Default")
      (node (ref "0001001") (pin "14") (pinfunction "CH3_14") (pintype "bidirectional"))
      (node (ref "R17") (pin "1") (pinfunction "1_1") (pintype "passive"))
      (node (ref "R18") (pin "1") (pinfunction "1_1") (pintype "passive"))
    )
    (net (code "14") (name "Net-(0001001-CH4)") (class "Default")
      (node (ref "0001001") (pin "15") (pinfunction "CH4_15") (pintype "bidirectional"))
      (node (ref "R15") (pin "1") (pinfunction "1_1") (pintype "passive"))
      (node (ref "R16") (pin "1") (pinfunction "1_1") (pintype "passive"))
    )
    (net (code "15") (name "Net-(0001001-CH5)") (class "Default")
      (node (ref "0001001") (pin "16") (pinfunction "CH5_16") (pintype "bidirectional"))
      (node (ref "R13") (pin "1") (pinfunction "1_1") (pintype "passive"))
      (node (ref "R14") (pin "1") (pinfunction "1_1") (pintype "passive"))
    )
    (net (code "16") (name "Net-(0001001-CH6)") (class "Default")
      (node (ref "0001001") (pin "17") (pinfunction "CH6_17") (pintype "bidirectional"))
      (node (ref "R11") (pin "1") (pinfunction "1_1") (pintype "passive"))
      (node (ref "R12") (pin "1") (pinfunction "1_1") (pintype "passive"))
    )
    (net (code "17") (name "Net-(0001001-CH7)") (class "Default")
      (node (ref "0001001") (pin "18") (pinfunction "CH7_18") (pintype "bidirectional"))
      (node (ref "R10") (pin "1") (pinfunction "1_1") (pintype "passive"))
      (node (ref "R9") (pin "1") (pinfunction "1_1") (pintype "passive"))
    )
    (net (code "18") (name "Net-(0001001-REFCOMP)") (class "Default")
      (node (ref "0001001") (pin "1") (pinfunction "REFCOMP_1") (pintype "bidirectional"))
      (node (ref "C10") (pin "1") (pinfunction "1_1") (pintype "passive"))
      (node (ref "C11") (pin "1") (pinfunction "1_1") (pintype "passive"))
    )
    (net (code "19") (name "Net-(0001001-VREF)") (class "Default")
      (node (ref "0001001") (pin "20") (pinfunction "VREF_20") (pintype "bidirectional"))
      (node (ref "C12") (pin "1") (pinfunction "1_1") (pintype "passive"))
    )
    (net (code "20") (name "Net-(0001010-CH0)") (class "Default")
      (node (ref "0001010") (pin "11") (pinfunction "CH0_11") (pintype "bidirectional"))
      (node (ref "R37") (pin "1") (pinfunction "1_1") (pintype "passive"))
      (node (ref "R38") (pin "1") (pinfunction "1_1") (pintype "passive"))
    )
    (net (code "21") (name "Net-(0001010-CH1)") (class "Default")
      (node (ref "0001010") (pin "12") (pinfunction "CH1_12") (pintype "bidirectional"))
      (node (ref "R35") (pin "1") (pinfunction "1_1") (pintype "passive"))
      (node (ref "R36") (pin "1") (pinfunction "1_1") (pintype "passive"))
    )
    (net (code "22") (name "Net-(0001010-CH2)") (class "Default")
      (node (ref "0001010") (pin "13") (pinfunction "CH2_13") (pintype "bidirectional"))
      (node (ref "R33") (pin "1") (pinfunction "1_1") (pintype "passive"))
      (node (ref "R34") (pin "1") (pinfunction "1_1") (pintype "passive"))
    )
    (net (code "23") (name "Net-(0001010-CH3)") (class "Default")
      (node (ref "0001010") (pin "14") (pinfunction "CH3_14") (pintype "bidirectional"))
      (node (ref "R31") (pin "1") (pinfunction "1_1") (pintype "passive"))
      (node (ref "R32") (pin "1") (pinfunction "1_1") (pintype "passive"))
    )
    (net (code "24") (name "Net-(0001010-CH4)") (class "Default")
      (node (ref "0001010") (pin "15") (pinfunction "CH4_15") (pintype "bidirectional"))
      (node (ref "R29") (pin "1") (pinfunction "1_1") (pintype "passive"))
      (node (ref "R30") (pin "1") (pinfunction "1_1") (pintype "passive"))
    )
    (net (code "25") (name "Net-(0001010-CH5)") (class "Default")
      (node (ref "0001010") (pin "16") (pinfunction "CH5_16") (pintype "bidirectional"))
      (node (ref "R27") (pin "1") (pinfunction "1_1") (pintype "passive"))
      (node (ref "R28") (pin "1") (pinfunction "1_1") (pintype "passive"))
    )
    (net (code "26") (name "Net-(0001010-CH6)") (class "Default")
      (node (ref "0001010") (pin "17") (pinfunction "CH6_17") (pintype "bidirectional"))
      (node (ref "R25") (pin "1") (pinfunction "1_1") (pintype "passive"))
      (node (ref "R26") (pin "1") (pinfunction "1_1") (pintype "passive"))
    )
    (net (code "27") (name "Net-(0001010-CH7)") (class "Default")
      (node (ref "0001010") (pin "18") (pinfunction "CH7_18") (pintype "bidirectional"))
      (node (ref "R39") (pin "1") (pinfunction "1_1") (pintype "passive"))
      (node (ref "R40") (pin "1") (pinfunction "1_1") (pintype "passive"))
    )
    (net (code "28") (name "Net-(0001010-REFCOMP)") (class "Default")
      (node (ref "0001010") (pin "1") (pinfunction "REFCOMP_1") (pintype "bidirectional"))
      (node (ref "C13") (pin "1") (pinfunction "1_1") (pintype "passive"))
      (node (ref "C14") (pin "1") (pinfunction "1_1") (pintype "passive"))
    )
    (net (code "29") (name "Net-(0001010-VREF)") (class "Default")
      (node (ref "0001010") (pin "20") (pinfunction "VREF_20") (pintype "bidirectional"))
      (node (ref "C18") (pin "1") (pinfunction "1_1") (pintype "passive"))
    )
    (net (code "30") (name "Net-(0001011-CH0)") (class "Default")
      (node (ref "0001011") (pin "11") (pinfunction "CH0_11") (pintype "bidirectional"))
      (node (ref "R55") (pin "1") (pinfunction "1_1") (pintype "passive"))
      (node (ref "R56") (pin "1") (pinfunction "1_1") (pintype "passive"))
    )
    (net (code "31") (name "Net-(0001011-CH1)") (class "Default")
      (node (ref "0001011") (pin "12") (pinfunction "CH1_12") (pintype "bidirectional"))
      (node (ref "R53") (pin "1") (pinfunction "1_1") (pintype "passive"))
      (node (ref "R54") (pin "1") (pinfunction "1_1") (pintype "passive"))
    )
    (net (code "32") (name "Net-(0001011-CH2)") (class "Default")
      (node (ref "0001011") (pin "13") (pinfunction "CH2_13") (pintype "bidirectional"))
      (node (ref "R51") (pin "1") (pinfunction "1_1") (pintype "passive"))
      (node (ref "R52") (pin "1") (pinfunction "1_1") (pintype "passive"))
    )
    (net (code "33") (name "Net-(0001011-CH3)") (class "Default")
      (node (ref "0001011") (pin "14") (pinfunction "CH3_14") (pintype "bidirectional"))
      (node (ref "R49") (pin "1") (pinfunction "1_1") (pintype "passive"))
      (node (ref "R50") (pin "1") (pinfunction "1_1") (pintype "passive"))
    )
    (net (code "34") (name "Net-(0001011-CH4)") (class "Default")
      (node (ref "0001011") (pin "15") (pinfunction "CH4_15") (pintype "bidirectional"))
      (node (ref "R41") (pin "1") (pinfunction "1_1") (pintype "passive"))
      (node (ref "R42") (pin "1") (pinfunction "1_1") (pintype "passive"))
    )
    (net (code "35") (name "Net-(0001011-CH5)") (class "Default")
      (node (ref "0001011") (pin "16") (pinfunction "CH5_16") (pintype "bidirectional"))
      (node (ref "R43") (pin "1") (pinfunction "1_1") (pintype "passive"))
      (node (ref "R44") (pin "1") (pinfunction "1_1") (pintype "passive"))
    )
    (net (code "36") (name "Net-(0001011-CH6)") (class "Default")
      (node (ref "0001011") (pin "17") (pinfunction "CH6_17") (pintype "bidirectional"))
      (node (ref "R45") (pin "1") (pinfunction "1_1") (pintype "passive"))
      (node (ref "R46") (pin "1") (pinfunction "1_1") (pintype "passive"))
    )
    (net (code "37") (name "Net-(0001011-CH7)") (class "Default")
      (node (ref "0001011") (pin "18") (pinfunction "CH7_18") (pintype "bidirectional"))
      (node (ref "R47") (pin "1") (pinfunction "1_1") (pintype "passive"))
      (node (ref "R48") (pin "1") (pinfunction "1_1") (pintype "passive"))
    )
    (net (code "38") (name "Net-(0001011-REFCOMP)") (class "Default")
      (node (ref "0001011") (pin "1") (pinfunction "REFCOMP_1") (pintype "bidirectional"))
      (node (ref "C19") (pin "1") (pinfunction "1_1") (pintype "passive"))
      (node (ref "C20") (pin "1") (pinfunction "1_1") (pintype "passive"))
    )
    (net (code "39") (name "Net-(0001011-VREF)") (class "Default")
      (node (ref "0001011") (pin "20") (pinfunction "VREF_20") (pintype "bidirectional"))
      (node (ref "C24") (pin "1") (pinfunction "1_1") (pintype "passive"))
    )
    (net (code "40") (name "Net-(0011000-CH0)") (class "Default")
      (node (ref "0011000") (pin "11") (pinfunction "CH0_11") (pintype "bidirectional"))
      (node (ref "R71") (pin "1") (pinfunction "1_1") (pintype "passive"))
      (node (ref "R72") (pin "1") (pinfunction "1_1") (pintype "passive"))
    )
    (net (code "41") (name "Net-(0011000-CH1)") (class "Default")
      (node (ref "0011000") (pin "12") (pinfunction "CH1_12") (pintype "bidirectional"))
      (node (ref "R69") (pin "1") (pinfunction "1_1") (pintype "passive"))
      (node (ref "R70") (pin "1") (pinfunction "1_1") (pintype "passive"))
    )
    (net (code "42") (name "Net-(0011000-CH2)") (class "Default")
      (node (ref "0011000") (pin "13") (pinfunction "CH2_13") (pintype "bidirectional"))
      (node (ref "R67") (pin "1") (pinfunction "1_1") (pintype "passive"))
      (node (ref "R68") (pin "1") (pinfunction "1_1") (pintype "passive"))
    )
    (net (code "43") (name "Net-(0011000-CH3)") (class "Default")
      (node (ref "0011000") (pin "14") (pinfunction "CH3_14") (pintype "bidirectional"))
      (node (ref "R65") (pin "1") (pinfunction "1_1") (pintype "passive"))
      (node (ref "R66") (pin "1") (pinfunction "1_1") (pintype "passive"))
    )
    (net (code "44") (name "Net-(0011000-CH4)") (class "Default")
      (node (ref "0011000") (pin "15") (pinfunction "CH4_15") (pintype "bidirectional"))
      (node (ref "R57") (pin "1") (pinfunction "1_1") (pintype "passive"))
      (node (ref "R58") (pin "1") (pinfunction "1_1") (pintype "passive"))
    )
    (net (code "45") (name "Net-(0011000-CH5)") (class "Default")
      (node (ref "0011000") (pin "16") (pinfunction "CH5_16") (pintype "bidirectional"))
      (node (ref "R59") (pin "1") (pinfunction "1_1") (pintype "passive"))
      (node (ref "R60") (pin "1") (pinfunction "1_1") (pintype "passive"))
    )
    (net (code "46") (name "Net-(0011000-CH6)") (class "Default")
      (node (ref "0011000") (pin "17") (pinfunction "CH6_17") (pintype "bidirectional"))
      (node (ref "R61") (pin "1") (pinfunction "1_1") (pintype "passive"))
      (node (ref "R62") (pin "1") (pinfunction "1_1") (pintype "passive"))
    )
    (net (code "47") (name "Net-(0011000-CH7)") (class "Default")
      (node (ref "0011000") (pin "18") (pinfunction "CH7_18") (pintype "bidirectional"))
      (node (ref "R63") (pin "1") (pinfunction "1_1") (pintype "passive"))
      (node (ref "R64") (pin "1") (pinfunction "1_1") (pintype "passive"))
    )
    (net (code "48") (name "Net-(0011000-REFCOMP)") (class "Default")
      (node (ref "0011000") (pin "1") (pinfunction "REFCOMP_1") (pintype "bidirectional"))
      (node (ref "C25") (pin "1") (pinfunction "1_1") (pintype "passive"))
      (node (ref "C26") (pin "1") (pinfunction "1_1") (pintype "passive"))
    )
    (net (code "49") (name "Net-(0011000-VREF)") (class "Default")
      (node (ref "0011000") (pin "20") (pinfunction "VREF_20") (pintype "bidirectional"))
      (node (ref "C30") (pin "1") (pinfunction "1_1") (pintype "passive"))
    )
    (net (code "50") (name "Net-(0011001-CH0)") (class "Default")
      (node (ref "0011001") (pin "11") (pinfunction "CH0_11") (pintype "bidirectional"))
      (node (ref "R83") (pin "1") (pinfunction "1_1") (pintype "passive"))
      (node (ref "R84") (pin "1") (pinfunction "1_1") (pintype "passive"))
    )
    (net (code "51") (name "Net-(0011001-CH1)") (class "Default")
      (node (ref "0011001") (pin "12") (pinfunction "CH1_12") (pintype "bidirectional"))
      (node (ref "R81") (pin "1") (pinfunction "1_1") (pintype "passive"))
      (node (ref "R82") (pin "1") (pinfunction "1_1") (pintype "passive"))
    )
    (net (code "52") (name "Net-(0011001-CH2)") (class "Default")
      (node (ref "0011001") (pin "13") (pinfunction "CH2_13") (pintype "bidirectional"))
      (node (ref "R79") (pin "1") (pinfunction "1_1") (pintype "passive"))
      (node (ref "R80") (pin "1") (pinfunction "1_1") (pintype "passive"))
    )
    (net (code "53") (name "Net-(0011001-CH3)") (class "Default")
      (node (ref "0011001") (pin "14") (pinfunction "CH3_14") (pintype "bidirectional"))
      (node (ref "R77") (pin "1") (pinfunction "1_1") (pintype "passive"))
      (node (ref "R78") (pin "1") (pinfunction "1_1") (pintype "passive"))
    )
    (net (code "54") (name "Net-(0011001-CH4)") (class "Default")
      (node (ref "0011001") (pin "15") (pinfunction "CH4_15") (pintype "bidirectional"))
      (node (ref "R75") (pin "1") (pinfunction "1_1") (pintype "passive"))
      (node (ref "R76") (pin "1") (pinfunction "1_1") (pintype "passive"))
    )
    (net (code "55") (name "Net-(0011001-CH5)") (class "Default")
      (node (ref "0011001") (pin "16") (pinfunction "CH5_16") (pintype "bidirectional"))
      (node (ref "R73") (pin "1") (pinfunction "1_1") (pintype "passive"))
      (node (ref "R74") (pin "1") (pinfunction "1_1") (pintype "passive"))
    )
    (net (code "56") (name "Net-(0011001-REFCOMP)") (class "Default")
      (node (ref "0011001") (pin "1") (pinfunction "REFCOMP_1") (pintype "bidirectional"))
      (node (ref "C31") (pin "1") (pinfunction "1_1") (pintype "passive"))
      (node (ref "C32") (pin "1") (pinfunction "1_1") (pintype "passive"))
    )
    (net (code "57") (name "Net-(0011001-VREF)") (class "Default")
      (node (ref "0011001") (pin "20") (pinfunction "VREF_20") (pintype "bidirectional"))
      (node (ref "C36") (pin "1") (pinfunction "1_1") (pintype "passive"))
    )
    (net (code "58") (name "Net-(U$1-PCINT6{slash}XTAL1{slash}TOSC1)") (class "Default")
      (node (ref "C39") (pin "1") (pinfunction "1_1") (pintype "passive"))
      (node (ref "U$1") (pin "9") (pinfunction "PCINT6/XTAL1/TOSC1_9") (pintype "bidirectional"))
      (node (ref "Y1") (pin "2") (pinfunction "2_2") (pintype "passive"))
    )
    (net (code "59") (name "Net-(U$1-PCINT7{slash}XTAL2{slash}TOSC2)") (class "Default")
      (node (ref "C40") (pin "1") (pinfunction "1_1") (pintype "passive"))
      (node (ref "U$1") (pin "10") (pinfunction "PCINT7/XTAL2/TOSC2_10") (pintype "bidirectional"))
      (node (ref "Y1") (pin "1") (pinfunction "1_1") (pintype "passive"))
    )
    (net (code "60") (name "Net-(U2-C1+)") (class "Default")
      (node (ref "C43") (pin "1") (pinfunction "1_1") (pintype "passive"))
      (node (ref "U2") (pin "2") (pinfunction "C1+_2") (pintype "passive"))
    )
    (net (code "61") (name "Net-(U2-C1-)") (class "Default")
      (node (ref "C43") (pin "2") (pinfunction "2_2") (pintype "passive"))
      (node (ref "U2") (pin "4") (pinfunction "C1-_4") (pintype "passive"))
    )
    (net (code "62") (name "Net-(U2-C2+)") (class "Default")
      (node (ref "C44") (pin "1") (pinfunction "1_1") (pintype "passive"))
      (node (ref "U2") (pin "5") (pinfunction "C2+_5") (pintype "passive"))
    )
    (net (code "63") (name "Net-(U2-C2-)") (class "Default")
      (node (ref "C44") (pin "2") (pinfunction "2_2") (pintype "passive"))
      (node (ref "U2") (pin "6") (pinfunction "C2-_6") (pintype "passive"))
    )
    (net (code "64") (name "Net-(U2-V+)") (class "Default")
      (node (ref "C41") (pin "1") (pinfunction "1_1") (pintype "passive"))
      (node (ref "U2") (pin "3") (pinfunction "V+_3") (pintype "power_in"))
    )
    (net (code "65") (name "Net-(U2-V-)") (class "Default")
      (node (ref "C42") (pin "1") (pinfunction "1_1") (pintype "passive"))
      (node (ref "U2") (pin "7") (pinfunction "V-_7") (pintype "power_in"))
    )
    (net (code "66") (name "RESET") (class "Default")
      (node (ref "ISP1") (pin "5") (pinfunction "RST_5") (pintype "output"))
      (node (ref "R87") (pin "1") (pinfunction "1_1") (pintype "passive"))
      (node (ref "RESET_BTN") (pin "P$3") (pinfunction "P$2_P$3") (pintype "bidirectional"))
      (node (ref "RESET_BTN") (pin "P$4") (pinfunction "P$2_P$4") (pintype "bidirectional"))
      (node (ref "U$1") (pin "1") (pinfunction "PCINT14/RESET_1") (pintype "bidirectional"))
    )
    (net (code "67") (name "RX") (class "Default")
      (node (ref "TO_FCC") (pin "P$7") (pinfunction "7_P$7") (pintype "bidirectional"))
      (node (ref "U$1") (pin "2") (pinfunction "PCINT16/RXD_2") (pintype "bidirectional"))
      (node (ref "U2") (pin "9") (pinfunction "ROUT_9") (pintype "output"))
    )
    (net (code "68") (name "RX12") (class "Default")
      (node (ref "TO_FCC") (pin "P$2") (pinfunction "2_P$2") (pintype "bidirectional"))
      (node (ref "U2") (pin "8") (pinfunction "RIN_8") (pintype "input"))
    )
    (net (code "69") (name "SCK") (class "Default")
      (node (ref "ISP1") (pin "3") (pinfunction "SCK_3") (pintype "output"))
      (node (ref "U$1") (pin "19") (pinfunction "SCK/PCINT5_19") (pintype "bidirectional"))
    )
    (net (code "70") (name "SCL") (class "Default")
      (node (ref "0001000") (pin "6") (pinfunction "SCL_6") (pintype "bidirectional"))
      (node (ref "0001001") (pin "6") (pinfunction "SCL_6") (pintype "bidirectional"))
      (node (ref "0001010") (pin "6") (pinfunction "SCL_6") (pintype "bidirectional"))
      (node (ref "0001011") (pin "6") (pinfunction "SCL_6") (pintype "bidirectional"))
      (node (ref "0011000") (pin "6") (pinfunction "SCL_6") (pintype "bidirectional"))
      (node (ref "0011001") (pin "6") (pinfunction "SCL_6") (pintype "bidirectional"))
      (node (ref "R85") (pin "1") (pinfunction "1_1") (pintype "passive"))
      (node (ref "U$1") (pin "28") (pinfunction "ADC5/SCL/PCINT13_28") (pintype "bidirectional"))
    )
    (net (code "71") (name "SDA") (class "Default")
      (node (ref "0001000") (pin "7") (pinfunction "SDA_7") (pintype "bidirectional"))
      (node (ref "0001001") (pin "7") (pinfunction "SDA_7") (pintype "bidirectional"))
      (node (ref "0001010") (pin "7") (pinfunction "SDA_7") (pintype "bidirectional"))
      (node (ref "0001011") (pin "7") (pinfunction "SDA_7") (pintype "bidirectional"))
      (node (ref "0011000") (pin "7") (pinfunction "SDA_7") (pintype "bidirectional"))
      (node (ref "0011001") (pin "7") (pinfunction "SDA_7") (pintype "bidirectional"))
      (node (ref "R86") (pin "1") (pinfunction "1_1") (pintype "passive"))
      (node (ref "U$1") (pin "27") (pinfunction "ADC4/SDA/PCINT12_27") (pintype "bidirectional"))
    )
    (net (code "72") (name "SER_INVALID") (class "Default")
      (node (ref "U2") (pin "10") (pinfunction "~{INVALID}_10") (pintype "output"))
    )
    (net (code "73") (name "SIG1") (class "Default")
      (node (ref "TO_FCC") (pin "P$5") (pinfunction "5_P$5") (pintype "bidirectional"))
      (node (ref "U$1") (pin "26") (pinfunction "ADC3/PCINT11_26") (pintype "bidirectional"))
    )
    (net (code "74") (name "SIG2") (class "Default")
      (node (ref "TO_FCC") (pin "P$6") (pinfunction "6_P$6") (pintype "bidirectional"))
      (node (ref "U$1") (pin "25") (pinfunction "ADC2/PCINT10_25") (pintype "bidirectional"))
    )
    (net (code "75") (name "TX") (class "Default")
      (node (ref "TO_FCC") (pin "P$8") (pinfunction "8_P$8") (pintype "bidirectional"))
      (node (ref "U$1") (pin "3") (pinfunction "PCINT17/TXD_3") (pintype "bidirectional"))
      (node (ref "U2") (pin "11") (pinfunction "DIN_11") (pintype "input"))
    )
    (net (code "76") (name "TX12") (class "Default")
      (node (ref "TO_FCC") (pin "P$3") (pinfunction "3_P$3") (pintype "bidirectional"))
      (node (ref "U2") (pin "13") (pinfunction "DOUT_13") (pintype "output"))
    )
    (net (code "77") (name "V+") (class "Default")
      (node (ref "0001000") (pin "10") (pinfunction "VDD1_10") (pintype "bidirectional"))
      (node (ref "0001000") (pin "3") (pinfunction "VDD0_3") (pintype "bidirectional"))
      (node (ref "0001001") (pin "10") (pinfunction "VDD1_10") (pintype "bidirectional"))
      (node (ref "0001001") (pin "3") (pinfunction "VDD0_3") (pintype "bidirectional"))
      (node (ref "0001010") (pin "10") (pinfunction "VDD1_10") (pintype "bidirectional"))
      (node (ref "0001010") (pin "3") (pinfunction "VDD0_3") (pintype "bidirectional"))
      (node (ref "0001010") (pin "4") (pinfunction "AD0_4") (pintype "bidirectional"))
      (node (ref "0001011") (pin "10") (pinfunction "VDD1_10") (pintype "bidirectional"))
      (node (ref "0001011") (pin "3") (pinfunction "VDD0_3") (pintype "bidirectional"))
      (node (ref "0001011") (pin "4") (pinfunction "AD0_4") (pintype "bidirectional"))
      (node (ref "0011000") (pin "10") (pinfunction "VDD1_10") (pintype "bidirectional"))
      (node (ref "0011000") (pin "3") (pinfunction "VDD0_3") (pintype "bidirectional"))
      (node (ref "0011001") (pin "10") (pinfunction "VDD1_10") (pintype "bidirectional"))
      (node (ref "0011001") (pin "3") (pinfunction "VDD0_3") (pintype "bidirectional"))
      (node (ref "C1") (pin "1") (pinfunction "1_1") (pintype "passive"))
      (node (ref "C15") (pin "1") (pinfunction "1_1") (pintype "passive"))
      (node (ref "C16") (pin "1") (pinfunction "1_1") (pintype "passive"))
      (node (ref "C17") (pin "1") (pinfunction "1_1") (pintype "passive"))
      (node (ref "C2") (pin "1") (pinfunction "1_1") (pintype "passive"))
      (node (ref "C21") (pin "1") (pinfunction "1_1") (pintype "passive"))
      (node (ref "C22") (pin "1") (pinfunction "1_1") (pintype "passive"))
      (node (ref "C23") (pin "1") (pinfunction "1_1") (pintype "passive"))
      (node (ref "C27") (pin "1") (pinfunction "1_1") (pintype "passive"))
      (node (ref "C28") (pin "1") (pinfunction "1_1") (pintype "passive"))
      (node (ref "C29") (pin "1") (pinfunction "1_1") (pintype "passive"))
      (node (ref "C3") (pin "1") (pinfunction "1_1") (pintype "passive"))
      (node (ref "C33") (pin "1") (pinfunction "1_1") (pintype "passive"))
      (node (ref "C34") (pin "1") (pinfunction "1_1") (pintype "passive"))
      (node (ref "C35") (pin "1") (pinfunction "1_1") (pintype "passive"))
      (node (ref "C37") (pin "1") (pinfunction "1_1") (pintype "passive"))
      (node (ref "C38") (pin "1") (pinfunction "1_1") (pintype "passive"))
      (node (ref "C7") (pin "1") (pinfunction "1_1") (pintype "passive"))
      (node (ref "C8") (pin "1") (pinfunction "1_1") (pintype "passive"))
      (node (ref "C9") (pin "1") (pinfunction "1_1") (pintype "passive"))
      (node (ref "ISP1") (pin "2") (pinfunction "VCC_2") (pintype "power_in"))
      (node (ref "R85") (pin "2") (pinfunction "2_2") (pintype "passive"))
      (node (ref "R86") (pin "2") (pinfunction "2_2") (pintype "passive"))
      (node (ref "R87") (pin "2") (pinfunction "2_2") (pintype "passive"))
      (node (ref "TO_FCC") (pin "P$1") (pinfunction "1_P$1") (pintype "bidirectional"))
      (node (ref "U$1") (pin "20") (pinfunction "AVCC_20") (pintype "bidirectional"))
      (node (ref "U$1") (pin "7") (pinfunction "VCC_7") (pintype "bidirectional"))
      (node (ref "U2") (pin "15") (pinfunction "VCC_15") (pintype "power_in"))
      (node (ref "U2") (pin "16") (pinfunction "~{FORCEOFF}_16") (pintype "input"))
    )
    (net (code "78") (name "V1") (class "Default")
      (node (ref "0001000") (pin "11") (pinfunction "CH0_11") (pintype "bidirectional"))
      (node (ref "R91") (pin "2") (pinfunction "2_2") (pintype "passive"))
      (node (ref "U$3") (pin "1") (pinfunction "1_1") (pintype "bidirectional"))
    )
    (net (code "79") (name "V2") (class "Default")
      (node (ref "0001000") (pin "12") (pinfunction "CH1_12") (pintype "bidirectional"))
      (node (ref "R90") (pin "2") (pinfunction "2_2") (pintype "passive"))
      (node (ref "U$3") (pin "2") (pinfunction "2_2") (pintype "bidirectional"))
    )
    (net (code "80") (name "V3") (class "Default")
      (node (ref "0001000") (pin "13") (pinfunction "CH2_13") (pintype "bidirectional"))
      (node (ref "R89") (pin "2") (pinfunction "2_2") (pintype "passive"))
      (node (ref "U$3") (pin "3") (pinfunction "3_3") (pintype "bidirectional"))
    )
    (net (code "81") (name "V4") (class "Default")
      (node (ref "0001000") (pin "14") (pinfunction "CH3_14") (pintype "bidirectional"))
      (node (ref "R88") (pin "2") (pinfunction "2_2") (pintype "passive"))
      (node (ref "U$3") (pin "4") (pinfunction "4_4") (pintype "bidirectional"))
    )
    (net (code "82") (name "V5") (class "Default")
      (node (ref "R2") (pin "2") (pinfunction "2_2") (pintype "passive"))
      (node (ref "U$3") (pin "5") (pinfunction "5_5") (pintype "bidirectional"))
    )
    (net (code "83") (name "V6") (class "Default")
      (node (ref "R4") (pin "2") (pinfunction "2_2") (pintype "passive"))
      (node (ref "U$3") (pin "6") (pinfunction "6_6") (pintype "bidirectional"))
    )
    (net (code "84") (name "V7") (class "Default")
      (node (ref "R6") (pin "2") (pinfunction "2_2") (pintype "passive"))
      (node (ref "U$3") (pin "7") (pinfunction "7_7") (pintype "bidirectional"))
    )
    (net (code "85") (name "V8") (class "Default")
      (node (ref "R8") (pin "2") (pinfunction "2_2") (pintype "passive"))
      (node (ref "U$3") (pin "8") (pinfunction "8_8") (pintype "bidirectional"))
    )
    (net (code "86") (name "V9") (class "Default")
      (node (ref "R23") (pin "2") (pinfunction "2_2") (pintype "passive"))
      (node (ref "U$3") (pin "9") (pinfunction "9_9") (pintype "bidirectional"))
    )
    (net (code "87") (name "V10") (class "Default")
      (node (ref "R21") (pin "2") (pinfunction "2_2") (pintype "passive"))
      (node (ref "U$3") (pin "10") (pinfunction "10_10") (pintype "bidirectional"))
    )
    (net (code "88") (name "V11") (class "Default")
      (node (ref "R19") (pin "2") (pinfunction "2_2") (pintype "passive"))
      (node (ref "U$3") (pin "11") (pinfunction "11_11") (pintype "bidirectional"))
    )
    (net (code "89") (name "V12") (class "Default")
      (node (ref "R17") (pin "2") (pinfunction "2_2") (pintype "passive"))
      (node (ref "U$3") (pin "12") (pinfunction "12_12") (pintype "bidirectional"))
    )
    (net (code "90") (name "V13") (class "Default")
      (node (ref "R15") (pin "2") (pinfunction "2_2") (pintype "passive"))
      (node (ref "U$3") (pin "13") (pinfunction "13_13") (pintype "bidirectional"))
    )
    (net (code "91") (name "V14") (class "Default")
      (node (ref "R13") (pin "2") (pinfunction "2_2") (pintype "passive"))
      (node (ref "U$3") (pin "14") (pinfunction "14_14") (pintype "bidirectional"))
    )
    (net (code "92") (name "V15") (class "Default")
      (node (ref "R11") (pin "2") (pinfunction "2_2") (pintype "passive"))
      (node (ref "U$3") (pin "15") (pinfunction "15_15") (pintype "bidirectional"))
    )
    (net (code "93") (name "V16") (class "Default")
      (node (ref "R9") (pin "2") (pinfunction "2_2") (pintype "passive"))
      (node (ref "U$3") (pin "16") (pinfunction "16_16") (pintype "bidirectional"))
    )
    (net (code "94") (name "V17") (class "Default")
      (node (ref "R37") (pin "2") (pinfunction "2_2") (pintype "passive"))
      (node (ref "U$3") (pin "17") (pinfunction "17_17") (pintype "bidirectional"))
    )
    (net (code "95") (name "V18") (class "Default")
      (node (ref "R35") (pin "2") (pinfunction "2_2") (pintype "passive"))
      (node (ref "U$3") (pin "18") (pinfunction "18_18") (pintype "bidirectional"))
    )
    (net (code "96") (name "V19") (class "Default")
      (node (ref "R33") (pin "2") (pinfunction "2_2") (pintype "passive"))
      (node (ref "U$3") (pin "19") (pinfunction "19_19") (pintype "bidirectional"))
    )
    (net (code "97") (name "V20") (class "Default")
      (node (ref "R31") (pin "2") (pinfunction "2_2") (pintype "passive"))
      (node (ref "U$3") (pin "20") (pinfunction "20_20") (pintype "bidirectional"))
    )
    (net (code "98") (name "V21") (class "Default")
      (node (ref "R29") (pin "2") (pinfunction "2_2") (pintype "passive"))
      (node (ref "U$3") (pin "21") (pinfunction "21_21") (pintype "bidirectional"))
    )
    (net (code "99") (name "V22") (class "Default")
      (node (ref "R27") (pin "2") (pinfunction "2_2") (pintype "passive"))
      (node (ref "U$3") (pin "22") (pinfunction "22_22") (pintype "bidirectional"))
    )
    (net (code "100") (name "V23") (class "Default")
      (node (ref "R25") (pin "2") (pinfunction "2_2") (pintype "passive"))
      (node (ref "U$3") (pin "23") (pinfunction "23_23") (pintype "bidirectional"))
    )
    (net (code "101") (name "V24") (class "Default")
      (node (ref "R40") (pin "2") (pinfunction "2_2") (pintype "passive"))
      (node (ref "U$3") (pin "24") (pinfunction "24_24") (pintype "bidirectional"))
    )
    (net (code "102") (name "V25") (class "Default")
      (node (ref "R55") (pin "2") (pinfunction "2_2") (pintype "passive"))
      (node (ref "U$3") (pin "25") (pinfunction "25_25") (pintype "bidirectional"))
    )
    (net (code "103") (name "V26") (class "Default")
      (node (ref "R53") (pin "2") (pinfunction "2_2") (pintype "passive"))
      (node (ref "U$3") (pin "26") (pinfunction "26_26") (pintype "bidirectional"))
    )
    (net (code "104") (name "V27") (class "Default")
      (node (ref "R51") (pin "2") (pinfunction "2_2") (pintype "passive"))
      (node (ref "U$3") (pin "27") (pinfunction "27_27") (pintype "bidirectional"))
    )
    (net (code "105") (name "V28") (class "Default")
      (node (ref "R49") (pin "2") (pinfunction "2_2") (pintype "passive"))
      (node (ref "U$3") (pin "28") (pinfunction "28_28") (pintype "bidirectional"))
    )
    (net (code "106") (name "V29") (class "Default")
      (node (ref "R42") (pin "2") (pinfunction "2_2") (pintype "passive"))
      (node (ref "U$3") (pin "29") (pinfunction "29_29") (pintype "bidirectional"))
    )
    (net (code "107") (name "V30") (class "Default")
      (node (ref "R44") (pin "2") (pinfunction "2_2") (pintype "passive"))
      (node (ref "U$3") (pin "30") (pinfunction "30_30") (pintype "bidirectional"))
    )
    (net (code "108") (name "V31") (class "Default")
      (node (ref "R46") (pin "2") (pinfunction "2_2") (pintype "passive"))
      (node (ref "U$3") (pin "31") (pinfunction "31_31") (pintype "bidirectional"))
    )
    (net (code "109") (name "V32") (class "Default")
      (node (ref "R48") (pin "2") (pinfunction "2_2") (pintype "passive"))
      (node (ref "U$3") (pin "32") (pinfunction "32_32") (pintype "bidirectional"))
    )
    (net (code "110") (name "V33") (class "Default")
      (node (ref "R71") (pin "2") (pinfunction "2_2") (pintype "passive"))
      (node (ref "U$3") (pin "33") (pinfunction "33_33") (pintype "bidirectional"))
    )
    (net (code "111") (name "V34") (class "Default")
      (node (ref "R69") (pin "2") (pinfunction "2_2") (pintype "passive"))
      (node (ref "U$3") (pin "34") (pinfunction "34_34") (pintype "bidirectional"))
    )
    (net (code "112") (name "V35") (class "Default")
      (node (ref "R67") (pin "2") (pinfunction "2_2") (pintype "passive"))
      (node (ref "U$3") (pin "35") (pinfunction "35_35") (pintype "bidirectional"))
    )
    (net (code "113") (name "V36") (class "Default")
      (node (ref "R65") (pin "2") (pinfunction "2_2") (pintype "passive"))
      (node (ref "U$3") (pin "36") (pinfunction "36_36") (pintype "bidirectional"))
    )
    (net (code "114") (name "V37") (class "Default")
      (node (ref "R58") (pin "2") (pinfunction "2_2") (pintype "passive"))
      (node (ref "U$3") (pin "37") (pinfunction "37_37") (pintype "bidirectional"))
    )
    (net (code "115") (name "V38") (class "Default")
      (node (ref "R60") (pin "2") (pinfunction "2_2") (pintype "passive"))
      (node (ref "U$3") (pin "38") (pinfunction "38_38") (pintype "bidirectional"))
    )
    (net (code "116") (name "V39") (class "Default")
      (node (ref "R62") (pin "2") (pinfunction "2_2") (pintype "passive"))
      (node (ref "U$3") (pin "39") (pinfunction "39_39") (pintype "bidirectional"))
    )
    (net (code "117") (name "V40") (class "Default")
      (node (ref "R64") (pin "2") (pinfunction "2_2") (pintype "passive"))
      (node (ref "U$3") (pin "40") (pinfunction "40_40") (pintype "bidirectional"))
    )
    (net (code "118") (name "V41") (class "Default")
      (node (ref "R83") (pin "2") (pinfunction "2_2") (pintype "passive"))
      (node (ref "U$3") (pin "41") (pinfunction "41_41") (pintype "bidirectional"))
    )
    (net (code "119") (name "V42") (class "Default")
      (node (ref "R81") (pin "2") (pinfunction "2_2") (pintype "passive"))
      (node (ref "U$3") (pin "42") (pinfunction "42_42") (pintype "bidirectional"))
    )
    (net (code "120") (name "V43") (class "Default")
      (node (ref "R79") (pin "2") (pinfunction "2_2") (pintype "passive"))
      (node (ref "U$3") (pin "43") (pinfunction "43_43") (pintype "bidirectional"))
    )
    (net (code "121") (name "V44") (class "Default")
      (node (ref "R77") (pin "2") (pinfunction "2_2") (pintype "passive"))
      (node (ref "U$3") (pin "44") (pinfunction "44_44") (pintype "bidirectional"))
    )
    (net (code "122") (name "V45") (class "Default")
      (node (ref "R75") (pin "2") (pinfunction "2_2") (pintype "passive"))
      (node (ref "U$3") (pin "45") (pinfunction "45_45") (pintype "bidirectional"))
    )
    (net (code "123") (name "V46") (class "Default")
      (node (ref "R73") (pin "2") (pinfunction "2_2") (pintype "passive"))
      (node (ref "U$3") (pin "46") (pinfunction "46_46") (pintype "bidirectional"))
    )
    (net (code "124") (name "unconnected-(0001001-AD0-Pad4)") (class "Default")
      (node (ref "0001001") (pin "4") (pinfunction "AD0_4") (pintype "bidirectional"))
    )
    (net (code "125") (name "unconnected-(0001011-AD1-Pad5)") (class "Default")
      (node (ref "0001011") (pin "5") (pinfunction "AD1_5") (pintype "bidirectional"))
    )
    (net (code "126") (name "unconnected-(0011000-AD0-Pad4)") (class "Default")
      (node (ref "0011000") (pin "4") (pinfunction "AD0_4") (pintype "bidirectional"))
    )
    (net (code "127") (name "unconnected-(0011000-AD1-Pad5)") (class "Default")
      (node (ref "0011000") (pin "5") (pinfunction "AD1_5") (pintype "bidirectional"))
    )
    (net (code "128") (name "unconnected-(0011001-AD1-Pad5)") (class "Default")
      (node (ref "0011001") (pin "5") (pinfunction "AD1_5") (pintype "bidirectional"))
    )
    (net (code "129") (name "unconnected-(0011001-CH6-Pad17)") (class "Default")
      (node (ref "0011001") (pin "17") (pinfunction "CH6_17") (pintype "bidirectional"))
    )
    (net (code "130") (name "unconnected-(0011001-CH7-Pad18)") (class "Default")
      (node (ref "0011001") (pin "18") (pinfunction "CH7_18") (pintype "bidirectional"))
    )
    (net (code "131") (name "unconnected-(TO_FCC-LED1N-PadP$9)") (class "Default")
      (node (ref "TO_FCC") (pin "P$9") (pinfunction "LED1N_P$9") (pintype "bidirectional"))
    )
    (net (code "132") (name "unconnected-(TO_FCC-LED1P-PadP$10)") (class "Default")
      (node (ref "TO_FCC") (pin "P$10") (pinfunction "LED1P_P$10") (pintype "bidirectional"))
    )
    (net (code "133") (name "unconnected-(TO_FCC-LED2N-PadP$11)") (class "Default")
      (node (ref "TO_FCC") (pin "P$11") (pinfunction "LED2N_P$11") (pintype "bidirectional"))
    )
    (net (code "134") (name "unconnected-(TO_FCC-LED2P-PadP$12)") (class "Default")
      (node (ref "TO_FCC") (pin "P$12") (pinfunction "LED2P_P$12") (pintype "bidirectional"))
    )
    (net (code "135") (name "unconnected-(U$1-ADC0{slash}PCINT8-Pad23)") (class "Default")
      (node (ref "U$1") (pin "23") (pinfunction "ADC0/PCINT8_23") (pintype "bidirectional"))
    )
    (net (code "136") (name "unconnected-(U$1-ADC1{slash}PCINT9-Pad24)") (class "Default")
      (node (ref "U$1") (pin "24") (pinfunction "ADC1/PCINT9_24") (pintype "bidirectional"))
    )
    (net (code "137") (name "unconnected-(U$1-AREF-Pad21)") (class "Default")
      (node (ref "U$1") (pin "21") (pinfunction "AREF_21") (pintype "bidirectional"))
    )
    (net (code "138") (name "unconnected-(U$1-OC1A{slash}PCINT1-Pad15)") (class "Default")
      (node (ref "U$1") (pin "15") (pinfunction "OC1A/PCINT1_15") (pintype "bidirectional"))
    )
    (net (code "139") (name "unconnected-(U$1-PCINT0{slash}CLKO{slash}ICP1-Pad14)") (class "Default")
      (node (ref "U$1") (pin "14") (pinfunction "PCINT0/CLKO/ICP1_14") (pintype "bidirectional"))
    )
    (net (code "140") (name "unconnected-(U$1-PCINT18{slash}INT0-Pad4)") (class "Default")
      (node (ref "U$1") (pin "4") (pinfunction "PCINT18/INT0_4") (pintype "bidirectional"))
    )
    (net (code "141") (name "unconnected-(U$1-PCINT19{slash}OC2B{slash}INT1-Pad5)") (class "Default")
      (node (ref "U$1") (pin "5") (pinfunction "PCINT19/OC2B/INT1_5") (pintype "bidirectional"))
    )
    (net (code "142") (name "unconnected-(U$1-PCINT20{slash}XCK{slash}T0-Pad6)") (class "Default")
      (node (ref "U$1") (pin "6") (pinfunction "PCINT20/XCK/T0_6") (pintype "bidirectional"))
    )
    (net (code "143") (name "unconnected-(U$1-PCINT21{slash}OC0B{slash}T1-Pad11)") (class "Default")
      (node (ref "U$1") (pin "11") (pinfunction "PCINT21/OC0B/T1_11") (pintype "bidirectional"))
    )
    (net (code "144") (name "unconnected-(U$1-PCINT22{slash}OC0A{slash}AIN0-Pad12)") (class "Default")
      (node (ref "U$1") (pin "12") (pinfunction "PCINT22/OC0A/AIN0_12") (pintype "bidirectional"))
    )
    (net (code "145") (name "unconnected-(U$1-PCINT23{slash}AIN1-Pad13)") (class "Default")
      (node (ref "U$1") (pin "13") (pinfunction "PCINT23/AIN1_13") (pintype "bidirectional"))
    )
    (net (code "146") (name "unconnected-(U$1-SS{slash}OC1B{slash}PCINT2-Pad16)") (class "Default")
      (node (ref "U$1") (pin "16") (pinfunction "SS/OC1B/PCINT2_16") (pintype "bidirectional"))
    )
    (net (code "147") (name "unconnected-(U$3-Pad48)") (class "Default")
      (node (ref "U$3") (pin "48") (pinfunction "48_48") (pintype "bidirectional"))
    )
  )
)
